# SmartDoor.net
KiCad netlist of a schematic drawn in Altium Designer
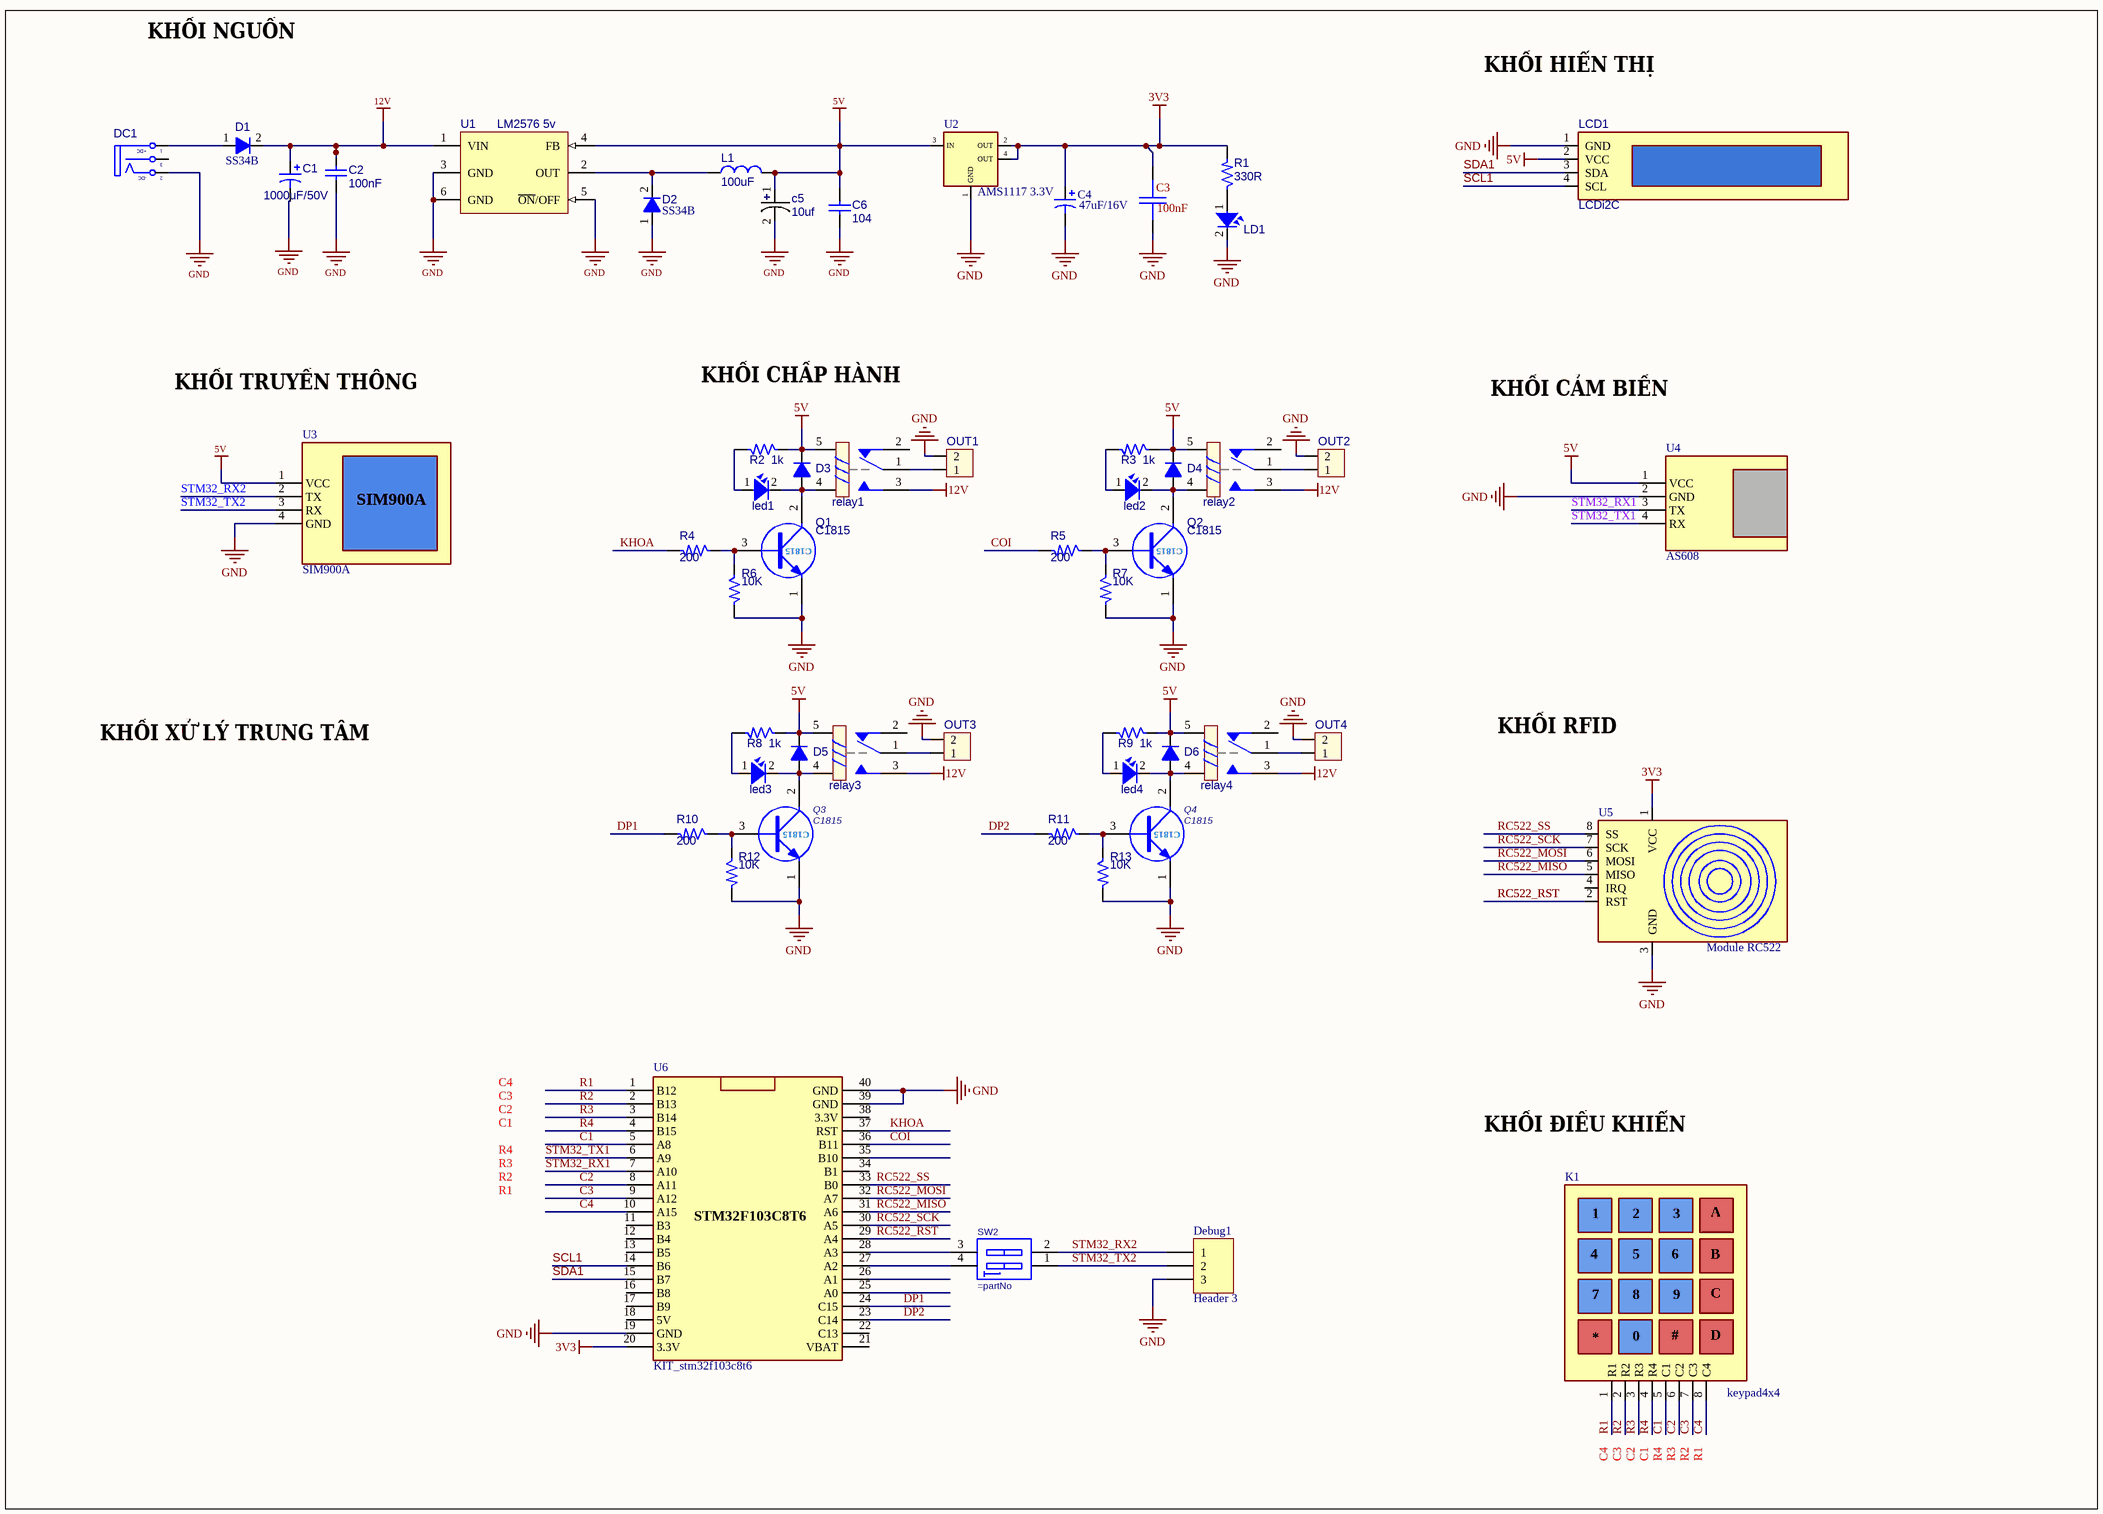
[diagram p0: SmartDoor.SchDoc]

(export (version "E")
  (design (tool "Eeschema 10.0.6"))
  (components
    (comp (ref "C1")
      (value "1000uF/50V")
      (footprint "C_EL_10_12")
      (description "Polarized Capacitor (Radial)")
      (fields (field (name "Comment") "1000uF-50V-DIP") (field (name "PUBLISHER") "Altium Limited"))
      (libsource (lib "Miscellaneous Devices") (part "Cap Pol1"))
    )
    (comp (ref "C2")
      (value "100nF")
      (footprint "C0805S")
      (description "Capacitor")
      (fields (field (name "Comment") "100nF-50V-126") (field (name "PUBLISHER") "Altium Limited"))
      (libsource (lib "Miscellaneous Devices") (part "Cap"))
    )
    (comp (ref "C3")
      (value "100nF")
      (footprint "C0805S")
      (description "Capacitor, Ceramic Chip, 16V, X7R, 10%")
      (fields
        (field (name "MANUFACTURER") "Samsung Electromechanics")
        (field (name "PARTNUMBER") "CL05B104KO5NNNC")
      )
      (libsource (lib "PADSlegacy_Passive") (part "C0402"))
    )
    (comp (ref "C4")
      (value "47uF/16V")
      (footprint "6032")
      (description "Polarized Capacitor (Radial)")
      (fields (field (name "Comment") "Tanta-47uF-16V-2917") (field (name "PUBLISHER") "Altium Limited"))
      (libsource (lib "Miscellaneous Devices") (part "Cap Pol1"))
    )
    (comp (ref "c5")
      (value "10uf")
      (footprint "C_EL_10_9")
      (libsource (lib "Schlib_do_an_2019") (part "radial"))
    )
    (comp (ref "C6")
      (value "104")
      (footprint "C0805S")
      (description "Capacitor (Semiconductor SIM Model)")
      (fields (field (name "PUBLISHER") "Altium Limited"))
      (libsource (lib "Pcblib_do_an_2019") (part "Cap 104_SMD"))
    )
    (comp (ref "D1") (value "SS34B") (footprint "D_SMB") (libsource (lib "Schlib_do_an_2019") (part "diode")))
    (comp (ref "D2") (value "SS34B") (footprint "D_SMB") (libsource (lib "Schlib_do_an_2019") (part "diode")))
    (comp (ref "D3") (value "diode") (footprint "D_SMA") (libsource (lib "Pcblib_do_an_2019") (part "diode")))
    (comp (ref "D4") (value "diode") (footprint "D_SMA") (libsource (lib "Pcblib_do_an_2019") (part "diode")))
    (comp (ref "D5") (value "diode") (footprint "D_SMA") (libsource (lib "Pcblib_do_an_2019") (part "diode")))
    (comp (ref "D6") (value "diode") (footprint "D_SMA") (libsource (lib "Pcblib_do_an_2019") (part "diode")))
    (comp (ref "DC1")
      (value "Jack DC5.5x2.5MM DC5525")
      (footprint "DC-IN")
      (description "Jac DC input")
      (libsource (lib "syhaunguyen") (part "DCIN"))
    )
    (comp (ref "Debug1")
      (value "Header 3")
      (footprint "HDR_M_1X3")
      (description "Header, 3-Pin")
      (fields (field (name "PUBLISHER") "Altium Limited"))
      (libsource (lib "Miscellaneous Connectors") (part "Header 3"))
    )
    (comp (ref "K1") (value "keypad4x4") (footprint "XH_8") (libsource (lib "kctm_lib") (part "keypad")))
    (comp (ref "L1")
      (value "100uF")
      (footprint "L_12")
      (description "Inductor")
      (libsource (lib "Lib_Chuan_03_08_2013") (part "L1"))
    )
    (comp (ref "LCD1") (value "LCDi2C") (footprint "XH_4") (libsource (lib "lib_vuon_dua") (part "LCDi2C")))
    (comp (ref "LD1")
      (value "led 0805 green")
      (footprint "LED0805GRN")
      (libsource (lib "Schlib_do_an_2019") (part "led"))
    )
    (comp (ref "led1")
      (value "led")
      (footprint "led 5mm red dip")
      (libsource (lib "Schlib_do_an_2019") (part "led"))
    )
    (comp (ref "led2")
      (value "led")
      (footprint "led 5mm red dip")
      (libsource (lib "Schlib_do_an_2019") (part "led"))
    )
    (comp (ref "led3")
      (value "led")
      (footprint "led 5mm red dip")
      (libsource (lib "Schlib_do_an_2019") (part "led"))
    )
    (comp (ref "led4")
      (value "led")
      (footprint "led 5mm red dip")
      (libsource (lib "Schlib_do_an_2019") (part "led"))
    )
    (comp (ref "OUT1")
      (value "con2")
      (footprint "MSTBF_2")
      (libsource (lib "Schlib_do_an_2019") (part "con2"))
    )
    (comp (ref "OUT2")
      (value "con2")
      (footprint "MSTBF_2")
      (libsource (lib "Schlib_do_an_2019") (part "con2"))
    )
    (comp (ref "OUT3")
      (value "con2")
      (footprint "MSTBF_2")
      (libsource (lib "Schlib_do_an_2019") (part "con2"))
    )
    (comp (ref "OUT4")
      (value "con2")
      (footprint "MSTBF_2")
      (libsource (lib "Schlib_do_an_2019") (part "con2"))
    )
    (comp (ref "Q1")
      (value "C1815")
      (footprint "VuNgocDang:TO-92W")
      (libsource (lib "Schlib_do_an_2019") (part "C1815"))
    )
    (comp (ref "Q2")
      (value "C1815")
      (footprint "VuNgocDang:TO-92W")
      (libsource (lib "Schlib_do_an_2019") (part "C1815"))
    )
    (comp (ref "Q3")
      (value "C1815")
      (footprint "TO-92B")
      (libsource (lib "Schlib_do_an_2019") (part "C1815"))
    )
    (comp (ref "Q4")
      (value "C1815")
      (footprint "TO-92B")
      (libsource (lib "Schlib_do_an_2019") (part "C1815"))
    )
    (comp (ref "R1")
      (value "330R")
      (footprint "R0805E")
      (description "Resistor 1/4W")
      (libsource (lib "library_2") (part "R"))
    )
    (comp (ref "R2")
      (value "1k")
      (footprint "R0805E")
      (description "Resistor 1/4W")
      (libsource (lib "Pcblib_do_an_2019") (part "R"))
    )
    (comp (ref "R3")
      (value "1k")
      (footprint "R0805E")
      (description "Resistor 1/4W")
      (libsource (lib "Pcblib_do_an_2019") (part "R"))
    )
    (comp (ref "R4")
      (value "200")
      (footprint "R0125W_AX03")
      (description "Resistor 1/4W")
      (libsource (lib "Pcblib_do_an_2019") (part "R"))
    )
    (comp (ref "R5")
      (value "200")
      (footprint "R0125W_AX03")
      (description "Resistor 1/4W")
      (libsource (lib "Pcblib_do_an_2019") (part "R"))
    )
    (comp (ref "R6")
      (value "10K")
      (footprint "R0805E")
      (description "Resistor 1/4W")
      (libsource (lib "Pcblib_do_an_2019") (part "R"))
    )
    (comp (ref "R7")
      (value "10K")
      (footprint "R0805E")
      (description "Resistor 1/4W")
      (libsource (lib "Pcblib_do_an_2019") (part "R"))
    )
    (comp (ref "R8")
      (value "1k")
      (footprint "R0805E")
      (description "Resistor 1/4W")
      (libsource (lib "Pcblib_do_an_2019") (part "R"))
    )
    (comp (ref "R9")
      (value "1k")
      (footprint "R0805E")
      (description "Resistor 1/4W")
      (libsource (lib "Pcblib_do_an_2019") (part "R"))
    )
    (comp (ref "R10")
      (value "200")
      (footprint "R0125W_AX03")
      (description "Resistor 1/4W")
      (libsource (lib "Pcblib_do_an_2019") (part "R"))
    )
    (comp (ref "R11")
      (value "200")
      (footprint "R0125W_AX03")
      (description "Resistor 1/4W")
      (libsource (lib "Pcblib_do_an_2019") (part "R"))
    )
    (comp (ref "R12")
      (value "10K")
      (footprint "R0805E")
      (description "Resistor 1/4W")
      (libsource (lib "Pcblib_do_an_2019") (part "R"))
    )
    (comp (ref "R13")
      (value "10K")
      (footprint "R0805E")
      (description "Resistor 1/4W")
      (libsource (lib "Pcblib_do_an_2019") (part "R"))
    )
    (comp (ref "relay1")
      (value "relay2")
      (footprint "RL_SPDT_10A")
      (libsource (lib "Schlib_do_an_2019") (part "relay2"))
    )
    (comp (ref "relay2")
      (value "relay2")
      (footprint "RL_SPDT_10A")
      (libsource (lib "Schlib_do_an_2019") (part "relay2"))
    )
    (comp (ref "relay3")
      (value "relay2")
      (footprint "RL_SPDT_10A")
      (libsource (lib "Schlib_do_an_2019") (part "relay2"))
    )
    (comp (ref "relay4")
      (value "relay2")
      (footprint "RL_SPDT_10A")
      (libsource (lib "Schlib_do_an_2019") (part "relay2"))
    )
    (comp (ref "SW2")
      (value "~")
      (footprint "SW2_DIP")
      (description "WS-DITV 2.54 mm small compact THT flat actuator with top tape")
      (fields
        (field (name "MANUFACTURER") "Wurth Elektronik")
        (field (name "PART NO.") "418127160902")
        (field (name "CREATED BY") "Baojun Chen")
      )
      (libsource (lib "LIBRARY") (part "SWDIP2"))
    )
    (comp (ref "U1")
      (value "LM2576 5v")
      (footprint "TO-263-5L, D2PAK-5, DDPAK, FMG170_5_S1000")
      (description "SIMPLE SWITCHER; 3A Step-Down Voltage Regulator")
      (fields
        (field (name "PARTNUMBER") "LM2576T-5.0")
        (field (name "MANUFACTURER") "National Semiconductor")
        (field (name "PUBLISHER") "Altium Limited")
      )
      (libsource (lib "Lib_Chuan_03_08_2013") (part "LM2576T-5.0"))
    )
    (comp (ref "U2")
      (value "AMS1117 3.3V")
      (footprint "TranVanDen:ASM1117-3V3")
      (libsource (lib "HF6200_Lib") (part "AMS1117"))
    )
    (comp (ref "U3") (value "SIM900A") (footprint "XH_4") (libsource (lib "SmartDoor") (part "SIM900A")))
    (comp (ref "U4") (value "AS608") (footprint "XH_4") (libsource (lib "user_lib") (part "R307")))
    (comp (ref "U5")
      (value "Module RC522")
      (footprint "XH_8")
      (libsource (lib "QuanLyHangHoa_Lib") (part "Module RC522"))
    )
    (comp (ref "U6")
      (value "KIT_stm32f103c8t6")
      (footprint "KIT_stm32f103")
      (libsource (lib "user_lib") (part "KIT_stm32f103c8t6"))
    )
  )
  (nets
    (net (code "1") (name "/C1") (class "Default")
      (node (ref "K1") (pin "5") (pinfunction "C1_5") (pintype "passive"))
      (node (ref "U6") (pin "5") (pinfunction "A8_5") (pintype "passive"))
    )
    (net (code "2") (name "/C2") (class "Default")
      (node (ref "K1") (pin "6") (pinfunction "C2_6") (pintype "passive"))
      (node (ref "U6") (pin "8") (pinfunction "A11_8") (pintype "passive"))
    )
    (net (code "3") (name "/C3") (class "Default")
      (node (ref "K1") (pin "7") (pinfunction "C3_7") (pintype "passive"))
      (node (ref "U6") (pin "9") (pinfunction "A12_9") (pintype "passive"))
    )
    (net (code "4") (name "/C4") (class "Default")
      (node (ref "K1") (pin "8") (pinfunction "C4_8") (pintype "passive"))
      (node (ref "U6") (pin "10") (pinfunction "A15_10") (pintype "passive"))
    )
    (net (code "5") (name "/COI") (class "Default")
      (node (ref "R5") (pin "2") (pinfunction "2_2") (pintype "passive"))
      (node (ref "U6") (pin "36") (pinfunction "B11_36") (pintype "passive"))
    )
    (net (code "6") (name "/DP1") (class "Default")
      (node (ref "R10") (pin "2") (pinfunction "2_2") (pintype "passive"))
      (node (ref "U6") (pin "24") (pinfunction "C15_24") (pintype "passive"))
    )
    (net (code "7") (name "/DP2") (class "Default")
      (node (ref "R11") (pin "2") (pinfunction "2_2") (pintype "passive"))
      (node (ref "U6") (pin "23") (pinfunction "C14_23") (pintype "passive"))
    )
    (net (code "8") (name "/KHOA") (class "Default")
      (node (ref "R4") (pin "2") (pinfunction "2_2") (pintype "passive"))
      (node (ref "U6") (pin "37") (pinfunction "RST_37") (pintype "passive"))
    )
    (net (code "9") (name "/R1") (class "Default")
      (node (ref "K1") (pin "1") (pinfunction "R1_1") (pintype "passive"))
      (node (ref "U6") (pin "1") (pinfunction "B12_1") (pintype "passive"))
    )
    (net (code "10") (name "/R2") (class "Default")
      (node (ref "K1") (pin "2") (pinfunction "R2_2") (pintype "passive"))
      (node (ref "U6") (pin "2") (pinfunction "B13_2") (pintype "passive"))
    )
    (net (code "11") (name "/R3") (class "Default")
      (node (ref "K1") (pin "3") (pinfunction "R3_3") (pintype "passive"))
      (node (ref "U6") (pin "3") (pinfunction "B14_3") (pintype "passive"))
    )
    (net (code "12") (name "/R4") (class "Default")
      (node (ref "K1") (pin "4") (pinfunction "R4_4") (pintype "passive"))
      (node (ref "U6") (pin "4") (pinfunction "B15_4") (pintype "passive"))
    )
    (net (code "13") (name "/RC522_MISO") (class "Default")
      (node (ref "U5") (pin "5") (pinfunction "MISO_5") (pintype "passive"))
      (node (ref "U6") (pin "31") (pinfunction "A6_31") (pintype "passive"))
    )
    (net (code "14") (name "/RC522_MOSI") (class "Default")
      (node (ref "U5") (pin "6") (pinfunction "MOSI_6") (pintype "passive"))
      (node (ref "U6") (pin "32") (pinfunction "A7_32") (pintype "passive"))
    )
    (net (code "15") (name "/RC522_RST") (class "Default")
      (node (ref "U5") (pin "2") (pinfunction "RST_2") (pintype "passive"))
      (node (ref "U6") (pin "29") (pinfunction "A4_29") (pintype "passive"))
    )
    (net (code "16") (name "/RC522_SCK") (class "Default")
      (node (ref "U5") (pin "7") (pinfunction "SCK_7") (pintype "passive"))
      (node (ref "U6") (pin "30") (pinfunction "A5_30") (pintype "passive"))
    )
    (net (code "17") (name "/RC522_SS") (class "Default")
      (node (ref "U5") (pin "8") (pinfunction "SS_8") (pintype "passive"))
      (node (ref "U6") (pin "33") (pinfunction "B0_33") (pintype "passive"))
    )
    (net (code "18") (name "/SCL1") (class "Default")
      (node (ref "LCD1") (pin "4") (pinfunction "SCL_4") (pintype "passive"))
      (node (ref "U6") (pin "14") (pinfunction "B6_14") (pintype "passive"))
    )
    (net (code "19") (name "/SDA1") (class "Default")
      (node (ref "LCD1") (pin "3") (pinfunction "SDA_3") (pintype "passive"))
      (node (ref "U6") (pin "15") (pinfunction "B7_15") (pintype "passive"))
    )
    (net (code "20") (name "/STM32_RX1") (class "Default")
      (node (ref "U4") (pin "3") (pinfunction "TX_3") (pintype "passive"))
      (node (ref "U6") (pin "7") (pinfunction "A10_7") (pintype "passive"))
    )
    (net (code "21") (name "/STM32_RX2") (class "Default")
      (node (ref "Debug1") (pin "1") (pinfunction "1_1") (pintype "passive"))
      (node (ref "SW2") (pin "2") (pinfunction "2_2") (pintype "passive"))
      (node (ref "U3") (pin "2") (pinfunction "TX_2") (pintype "passive"))
    )
    (net (code "22") (name "/STM32_TX1") (class "Default")
      (node (ref "U4") (pin "4") (pinfunction "RX_4") (pintype "passive"))
      (node (ref "U6") (pin "6") (pinfunction "A9_6") (pintype "passive"))
    )
    (net (code "23") (name "/STM32_TX2") (class "Default")
      (node (ref "Debug1") (pin "2") (pinfunction "2_2") (pintype "passive"))
      (node (ref "SW2") (pin "1") (pinfunction "1_1") (pintype "passive"))
      (node (ref "U3") (pin "3") (pinfunction "RX_3") (pintype "passive"))
    )
    (net (code "24") (name "3V3") (class "Default")
      (node (ref "C3") (pin "2") (pinfunction "2_2") (pintype "passive"))
      (node (ref "C4") (pin "1") (pinfunction "1_1") (pintype "passive"))
      (node (ref "R1") (pin "2") (pinfunction "2_2") (pintype "passive"))
      (node (ref "U2") (pin "2") (pinfunction "OUT_2") (pintype "passive"))
      (node (ref "U2") (pin "4") (pinfunction "OUT_4") (pintype "passive"))
      (node (ref "U5") (pin "1") (pinfunction "VCC_1") (pintype "passive"))
      (node (ref "U6") (pin "20") (pinfunction "3.3V_20") (pintype "passive"))
    )
    (net (code "25") (name "5V") (class "Default")
      (node (ref "C6") (pin "2") (pintype "passive"))
      (node (ref "D3") (pin "2") (pinfunction "K_2") (pintype "passive"))
      (node (ref "D4") (pin "2") (pinfunction "K_2") (pintype "passive"))
      (node (ref "D5") (pin "2") (pinfunction "K_2") (pintype "passive"))
      (node (ref "D6") (pin "2") (pinfunction "K_2") (pintype "passive"))
      (node (ref "L1") (pin "2") (pinfunction "2_2") (pintype "passive"))
      (node (ref "LCD1") (pin "2") (pinfunction "VCC_2") (pintype "passive"))
      (node (ref "R2") (pin "1") (pinfunction "1_1") (pintype "passive"))
      (node (ref "R3") (pin "1") (pinfunction "1_1") (pintype "passive"))
      (node (ref "R8") (pin "1") (pinfunction "1_1") (pintype "passive"))
      (node (ref "R9") (pin "1") (pinfunction "1_1") (pintype "passive"))
      (node (ref "U1") (pin "4") (pinfunction "FB_4") (pintype "input"))
      (node (ref "U2") (pin "3") (pinfunction "IN_3") (pintype "passive"))
      (node (ref "U3") (pin "1") (pinfunction "VCC_1") (pintype "passive"))
      (node (ref "U4") (pin "1") (pinfunction "VCC_1") (pintype "passive"))
      (node (ref "c5") (pin "1") (pinfunction "1_1") (pintype "passive"))
      (node (ref "relay1") (pin "5") (pinfunction "5_5") (pintype "passive"))
      (node (ref "relay2") (pin "5") (pinfunction "5_5") (pintype "passive"))
      (node (ref "relay3") (pin "5") (pinfunction "5_5") (pintype "passive"))
      (node (ref "relay4") (pin "5") (pinfunction "5_5") (pintype "passive"))
    )
    (net (code "26") (name "12V") (class "Default")
      (node (ref "C1") (pin "1") (pinfunction "1_1") (pintype "passive"))
      (node (ref "C2") (pin "1") (pinfunction "1_1") (pintype "passive"))
      (node (ref "D1") (pin "2") (pinfunction "K_2") (pintype "passive"))
      (node (ref "U1") (pin "1") (pinfunction "VIN_1") (pintype "power_in"))
      (node (ref "relay1") (pin "3") (pinfunction "3_3") (pintype "passive"))
      (node (ref "relay2") (pin "3") (pinfunction "3_3") (pintype "passive"))
      (node (ref "relay3") (pin "3") (pinfunction "3_3") (pintype "passive"))
      (node (ref "relay4") (pin "3") (pinfunction "3_3") (pintype "passive"))
    )
    (net (code "27") (name "GND") (class "Default")
      (node (ref "C1") (pin "2") (pinfunction "2_2") (pintype "passive"))
      (node (ref "C2") (pin "2") (pinfunction "2_2") (pintype "passive"))
      (node (ref "C3") (pin "1") (pinfunction "1_1") (pintype "passive"))
      (node (ref "C4") (pin "2") (pinfunction "2_2") (pintype "passive"))
      (node (ref "C6") (pin "1") (pintype "passive"))
      (node (ref "D2") (pin "1") (pinfunction "A_1") (pintype "passive"))
      (node (ref "DC1") (pin "2") (pinfunction "TN_2") (pintype "passive"))
      (node (ref "Debug1") (pin "3") (pinfunction "3_3") (pintype "passive"))
      (node (ref "LCD1") (pin "1") (pinfunction "GND_1") (pintype "passive"))
      (node (ref "LD1") (pin "2") (pinfunction "1_2") (pintype "passive"))
      (node (ref "OUT1") (pin "2") (pinfunction "2_2") (pintype "passive"))
      (node (ref "OUT2") (pin "2") (pinfunction "2_2") (pintype "passive"))
      (node (ref "OUT3") (pin "2") (pinfunction "2_2") (pintype "passive"))
      (node (ref "OUT4") (pin "2") (pinfunction "2_2") (pintype "passive"))
      (node (ref "Q1") (pin "1") (pinfunction "E_1") (pintype "passive"))
      (node (ref "Q2") (pin "1") (pinfunction "E_1") (pintype "passive"))
      (node (ref "Q3") (pin "1") (pinfunction "E_1") (pintype "passive"))
      (node (ref "Q4") (pin "1") (pinfunction "E_1") (pintype "passive"))
      (node (ref "R12") (pin "2") (pinfunction "2_2") (pintype "passive"))
      (node (ref "R13") (pin "2") (pinfunction "2_2") (pintype "passive"))
      (node (ref "R6") (pin "2") (pinfunction "2_2") (pintype "passive"))
      (node (ref "R7") (pin "2") (pinfunction "2_2") (pintype "passive"))
      (node (ref "U1") (pin "3") (pinfunction "GND_3") (pintype "power_in"))
      (node (ref "U1") (pin "5") (pinfunction "~{ON}/OFF_5") (pintype "input"))
      (node (ref "U1") (pin "6") (pinfunction "GND_6") (pintype "passive"))
      (node (ref "U2") (pin "1") (pinfunction "GND_1") (pintype "passive"))
      (node (ref "U3") (pin "4") (pinfunction "GND_4") (pintype "passive"))
      (node (ref "U4") (pin "2") (pinfunction "GND_2") (pintype "passive"))
      (node (ref "U5") (pin "3") (pinfunction "GND_3") (pintype "passive"))
      (node (ref "U6") (pin "19") (pinfunction "GND_19") (pintype "passive"))
      (node (ref "U6") (pin "39") (pinfunction "GND_39") (pintype "passive"))
      (node (ref "U6") (pin "40") (pinfunction "GND_40") (pintype "passive"))
      (node (ref "c5") (pin "2") (pinfunction "2_2") (pintype "passive"))
    )
    (net (code "28") (name "Net-(D1-A)") (class "Default")
      (node (ref "D1") (pin "1") (pinfunction "A_1") (pintype "passive"))
      (node (ref "DC1") (pin "1") (pinfunction "T_1") (pintype "passive"))
    )
    (net (code "29") (name "Net-(D2-K)") (class "Default")
      (node (ref "D2") (pin "2") (pinfunction "K_2") (pintype "passive"))
      (node (ref "L1") (pin "1") (pinfunction "1_1") (pintype "passive"))
      (node (ref "U1") (pin "2") (pinfunction "OUT_2") (pintype "power_in"))
    )
    (net (code "30") (name "Net-(D3-A)") (class "Default")
      (node (ref "D3") (pin "1") (pinfunction "A_1") (pintype "passive"))
      (node (ref "Q1") (pin "2") (pinfunction "C_2") (pintype "passive"))
      (node (ref "led1") (pin "2") (pinfunction "1_2") (pintype "passive"))
      (node (ref "relay1") (pin "4") (pinfunction "4_4") (pintype "passive"))
    )
    (net (code "31") (name "Net-(D4-A)") (class "Default")
      (node (ref "D4") (pin "1") (pinfunction "A_1") (pintype "passive"))
      (node (ref "Q2") (pin "2") (pinfunction "C_2") (pintype "passive"))
      (node (ref "led2") (pin "2") (pinfunction "1_2") (pintype "passive"))
      (node (ref "relay2") (pin "4") (pinfunction "4_4") (pintype "passive"))
    )
    (net (code "32") (name "Net-(D5-A)") (class "Default")
      (node (ref "D5") (pin "1") (pinfunction "A_1") (pintype "passive"))
      (node (ref "Q3") (pin "2") (pinfunction "C_2") (pintype "passive"))
      (node (ref "led3") (pin "2") (pinfunction "1_2") (pintype "passive"))
      (node (ref "relay3") (pin "4") (pinfunction "4_4") (pintype "passive"))
    )
    (net (code "33") (name "Net-(D6-A)") (class "Default")
      (node (ref "D6") (pin "1") (pinfunction "A_1") (pintype "passive"))
      (node (ref "Q4") (pin "2") (pinfunction "C_2") (pintype "passive"))
      (node (ref "led4") (pin "2") (pinfunction "1_2") (pintype "passive"))
      (node (ref "relay4") (pin "4") (pinfunction "4_4") (pintype "passive"))
    )
    (net (code "34") (name "Net-(LD1-A)") (class "Default")
      (node (ref "LD1") (pin "1") (pinfunction "A_1") (pintype "passive"))
      (node (ref "R1") (pin "1") (pinfunction "1_1") (pintype "passive"))
    )
    (net (code "35") (name "Net-(OUT1-Pad1)") (class "Default")
      (node (ref "OUT1") (pin "1") (pinfunction "1_1") (pintype "passive"))
      (node (ref "relay1") (pin "1") (pinfunction "1_1") (pintype "passive"))
    )
    (net (code "36") (name "Net-(OUT2-Pad1)") (class "Default")
      (node (ref "OUT2") (pin "1") (pinfunction "1_1") (pintype "passive"))
      (node (ref "relay2") (pin "1") (pinfunction "1_1") (pintype "passive"))
    )
    (net (code "37") (name "Net-(OUT3-Pad1)") (class "Default")
      (node (ref "OUT3") (pin "1") (pinfunction "1_1") (pintype "passive"))
      (node (ref "relay3") (pin "1") (pinfunction "1_1") (pintype "passive"))
    )
    (net (code "38") (name "Net-(OUT4-Pad1)") (class "Default")
      (node (ref "OUT4") (pin "1") (pinfunction "1_1") (pintype "passive"))
      (node (ref "relay4") (pin "1") (pinfunction "1_1") (pintype "passive"))
    )
    (net (code "39") (name "Net-(Q1-B)") (class "Default")
      (node (ref "Q1") (pin "3") (pinfunction "B_3") (pintype "passive"))
      (node (ref "R4") (pin "1") (pinfunction "1_1") (pintype "passive"))
      (node (ref "R6") (pin "1") (pinfunction "1_1") (pintype "passive"))
    )
    (net (code "40") (name "Net-(Q2-B)") (class "Default")
      (node (ref "Q2") (pin "3") (pinfunction "B_3") (pintype "passive"))
      (node (ref "R5") (pin "1") (pinfunction "1_1") (pintype "passive"))
      (node (ref "R7") (pin "1") (pinfunction "1_1") (pintype "passive"))
    )
    (net (code "41") (name "Net-(Q3-B)") (class "Default")
      (node (ref "Q3") (pin "3") (pinfunction "B_3") (pintype "passive"))
      (node (ref "R10") (pin "1") (pinfunction "1_1") (pintype "passive"))
      (node (ref "R12") (pin "1") (pinfunction "1_1") (pintype "passive"))
    )
    (net (code "42") (name "Net-(Q4-B)") (class "Default")
      (node (ref "Q4") (pin "3") (pinfunction "B_3") (pintype "passive"))
      (node (ref "R11") (pin "1") (pinfunction "1_1") (pintype "passive"))
      (node (ref "R13") (pin "1") (pinfunction "1_1") (pintype "passive"))
    )
    (net (code "43") (name "Net-(U6-A2)") (class "Default")
      (node (ref "SW2") (pin "4") (pinfunction "4_4") (pintype "passive"))
      (node (ref "U6") (pin "27") (pinfunction "A2_27") (pintype "passive"))
    )
    (net (code "44") (name "Net-(U6-A3)") (class "Default")
      (node (ref "SW2") (pin "3") (pinfunction "3_3") (pintype "passive"))
      (node (ref "U6") (pin "28") (pinfunction "A3_28") (pintype "passive"))
    )
    (net (code "45") (name "Net-(led1-A)") (class "Default")
      (node (ref "R2") (pin "2") (pinfunction "2_2") (pintype "passive"))
      (node (ref "led1") (pin "1") (pinfunction "A_1") (pintype "passive"))
    )
    (net (code "46") (name "Net-(led2-A)") (class "Default")
      (node (ref "R3") (pin "2") (pinfunction "2_2") (pintype "passive"))
      (node (ref "led2") (pin "1") (pinfunction "A_1") (pintype "passive"))
    )
    (net (code "47") (name "Net-(led3-A)") (class "Default")
      (node (ref "R8") (pin "2") (pinfunction "2_2") (pintype "passive"))
      (node (ref "led3") (pin "1") (pinfunction "A_1") (pintype "passive"))
    )
    (net (code "48") (name "Net-(led4-A)") (class "Default")
      (node (ref "R9") (pin "2") (pinfunction "2_2") (pintype "passive"))
      (node (ref "led4") (pin "1") (pinfunction "A_1") (pintype "passive"))
    )
    (net (code "49") (name "unconnected-(DC1-S-Pad3)") (class "Default")
      (node (ref "DC1") (pin "3") (pinfunction "S_3") (pintype "power_in"))
    )
    (net (code "50") (name "unconnected-(U5-IRQ-Pad4)") (class "Default")
      (node (ref "U5") (pin "4") (pinfunction "IRQ_4") (pintype "passive"))
    )
    (net (code "51") (name "unconnected-(U6-3.3V-Pad38)") (class "Default")
      (node (ref "U6") (pin "38") (pinfunction "3.3V_38") (pintype "passive"))
    )
    (net (code "52") (name "unconnected-(U6-5V-Pad18)") (class "Default")
      (node (ref "U6") (pin "18") (pinfunction "5V_18") (pintype "passive"))
    )
    (net (code "53") (name "unconnected-(U6-A0-Pad25)") (class "Default")
      (node (ref "U6") (pin "25") (pinfunction "A0_25") (pintype "passive"))
    )
    (net (code "54") (name "unconnected-(U6-A1-Pad26)") (class "Default")
      (node (ref "U6") (pin "26") (pinfunction "A1_26") (pintype "passive"))
    )
    (net (code "55") (name "unconnected-(U6-B1-Pad34)") (class "Default")
      (node (ref "U6") (pin "34") (pinfunction "B1_34") (pintype "passive"))
    )
    (net (code "56") (name "unconnected-(U6-B3-Pad11)") (class "Default")
      (node (ref "U6") (pin "11") (pinfunction "B3_11") (pintype "passive"))
    )
    (net (code "57") (name "unconnected-(U6-B4-Pad12)") (class "Default")
      (node (ref "U6") (pin "12") (pinfunction "B4_12") (pintype "passive"))
    )
    (net (code "58") (name "unconnected-(U6-B5-Pad13)") (class "Default")
      (node (ref "U6") (pin "13") (pinfunction "B5_13") (pintype "passive"))
    )
    (net (code "59") (name "unconnected-(U6-B8-Pad16)") (class "Default")
      (node (ref "U6") (pin "16") (pinfunction "B8_16") (pintype "passive"))
    )
    (net (code "60") (name "unconnected-(U6-B9-Pad17)") (class "Default")
      (node (ref "U6") (pin "17") (pinfunction "B9_17") (pintype "passive"))
    )
    (net (code "61") (name "unconnected-(U6-B10-Pad35)") (class "Default")
      (node (ref "U6") (pin "35") (pinfunction "B10_35") (pintype "passive"))
    )
    (net (code "62") (name "unconnected-(U6-C13-Pad22)") (class "Default")
      (node (ref "U6") (pin "22") (pinfunction "C13_22") (pintype "passive"))
    )
    (net (code "63") (name "unconnected-(U6-VBAT-Pad21)") (class "Default")
      (node (ref "U6") (pin "21") (pinfunction "VBAT_21") (pintype "passive"))
    )
    (net (code "64") (name "unconnected-(relay1-Pad2)") (class "Default")
      (node (ref "relay1") (pin "2") (pinfunction "2_2") (pintype "passive"))
    )
    (net (code "65") (name "unconnected-(relay2-Pad2)") (class "Default")
      (node (ref "relay2") (pin "2") (pinfunction "2_2") (pintype "passive"))
    )
    (net (code "66") (name "unconnected-(relay3-Pad2)") (class "Default")
      (node (ref "relay3") (pin "2") (pinfunction "2_2") (pintype "passive"))
    )
    (net (code "67") (name "unconnected-(relay4-Pad2)") (class "Default")
      (node (ref "relay4") (pin "2") (pinfunction "2_2") (pintype "passive"))
    )
  )
)
